# single_key_module.net
KiCad netlist of a schematic drawn in EAGLE
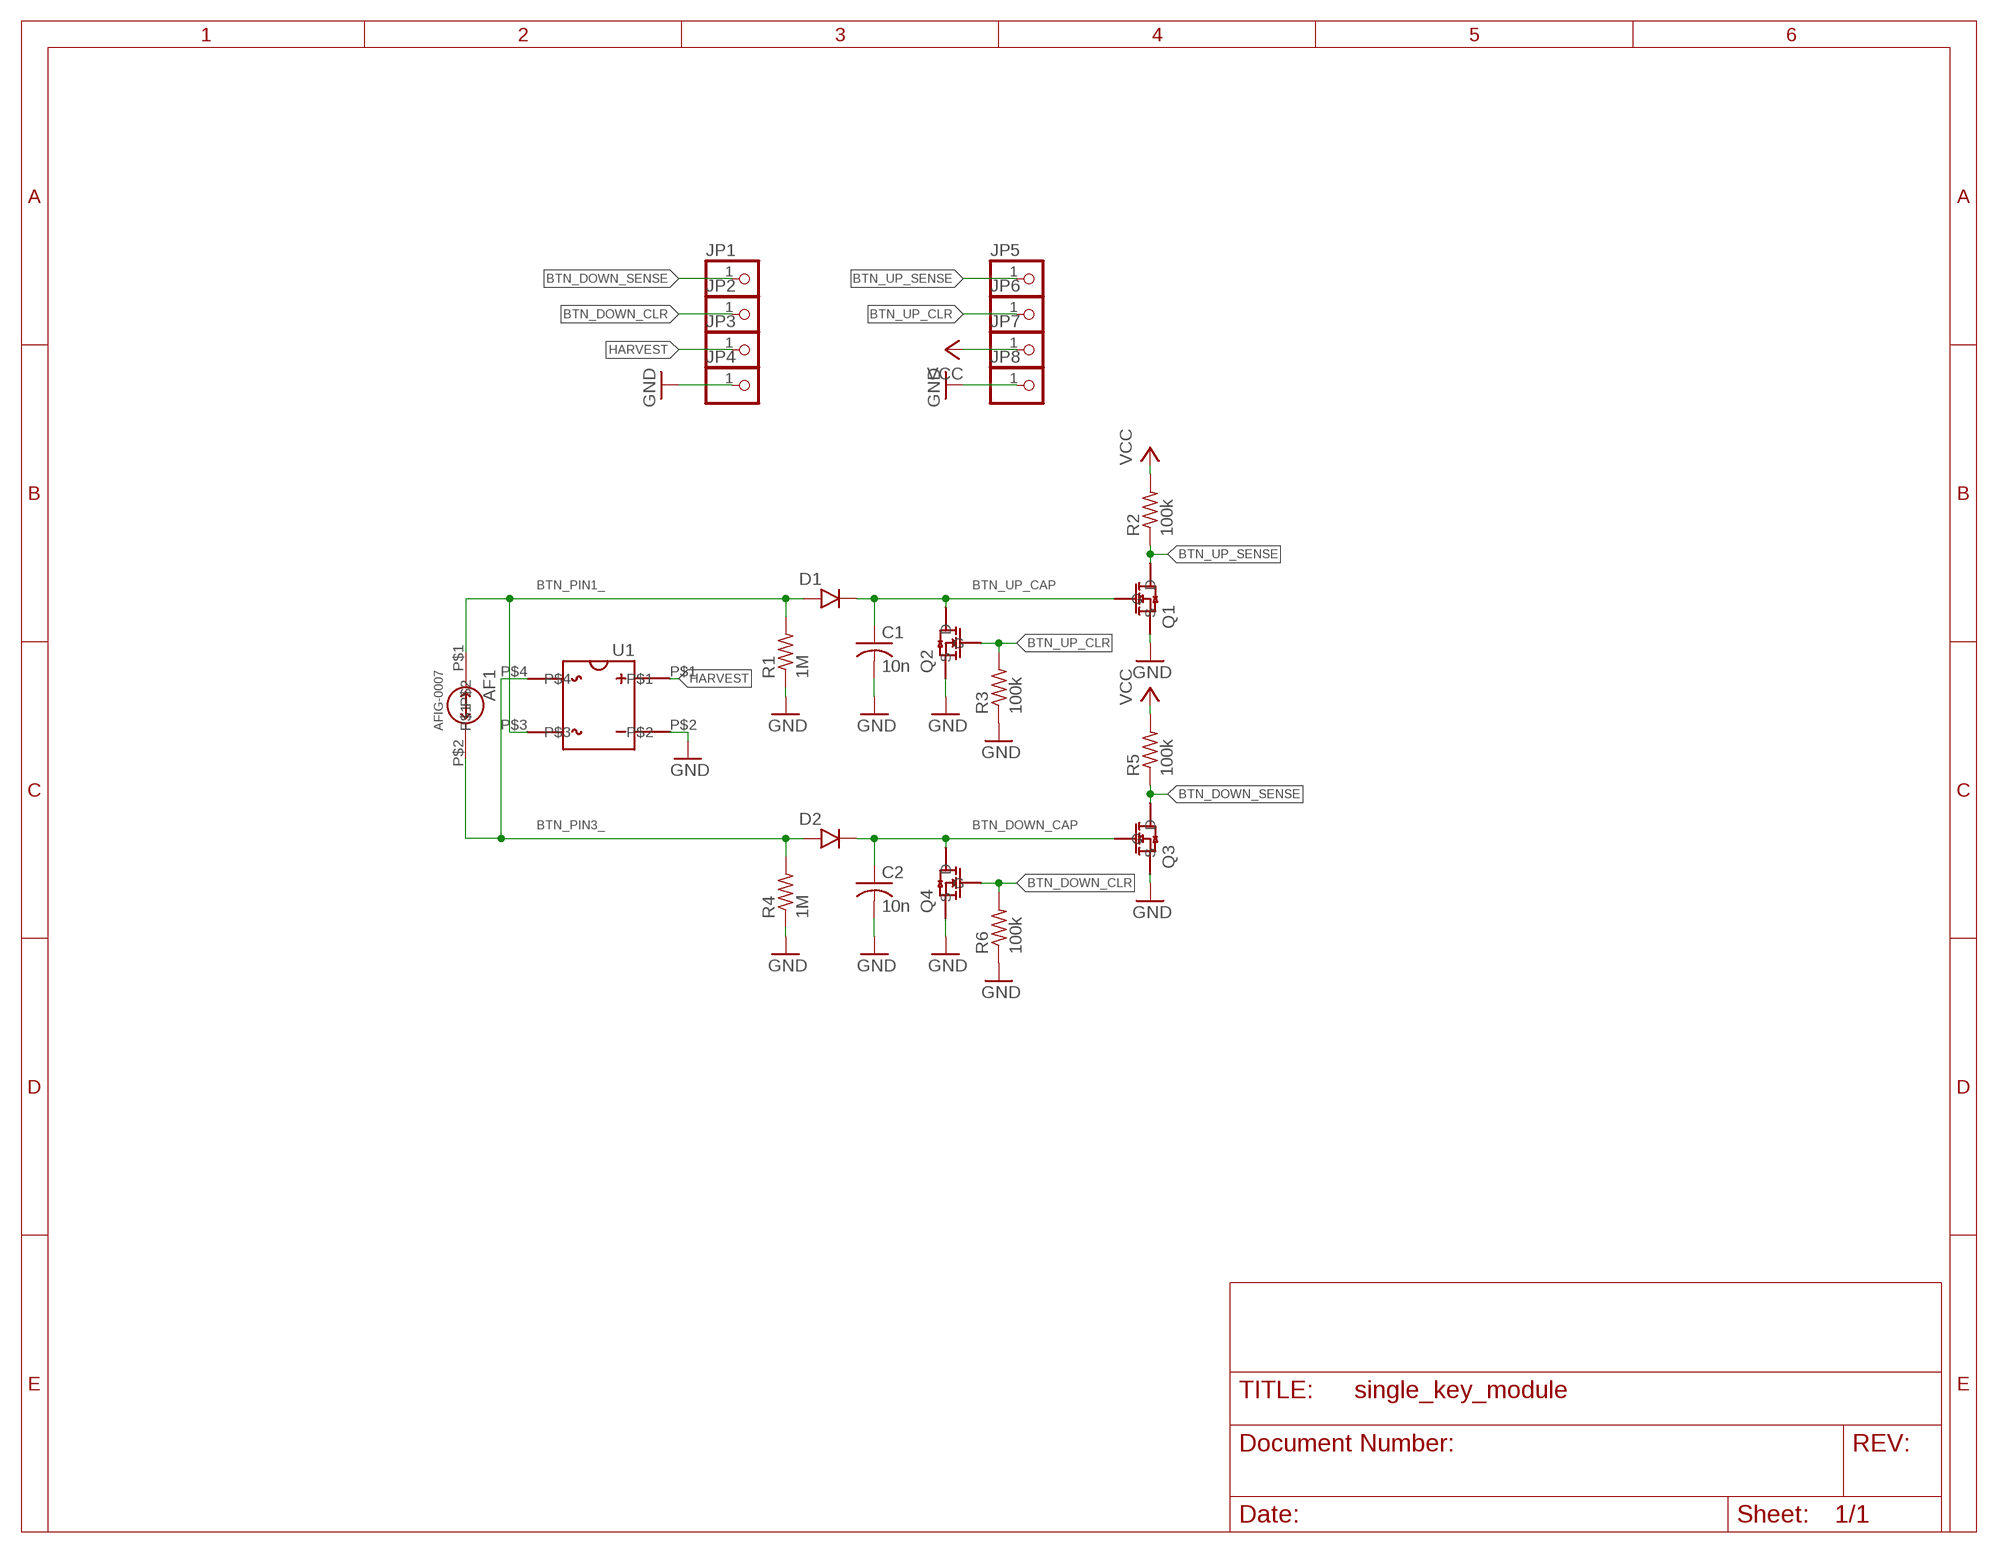
[diagram p0: schematic, sheet 1]

(export (version "E")
  (design (tool "Eeschema 10.0.6"))
  (components
    (comp (ref "AF1")
      (value "BUTTON-MOUNT")
      (footprint "eagle-import:BUTTON-MOUNT")
      (libsource (lib "eagle-import") (part "BUTTON-MOUNT"))
    )
    (comp (ref "C1")
      (value "10n")
      (footprint "eagle-import:C0402")
      (libsource (lib "eagle-import") (part "C-USC0402"))
    )
    (comp (ref "C2")
      (value "10n")
      (footprint "eagle-import:C0402")
      (libsource (lib "eagle-import") (part "C-USC0402"))
    )
    (comp (ref "D1")
      (value "DFLU1200")
      (footprint "eagle-import:DFLU1200")
      (libsource (lib "eagle-import") (part "DFLU1200"))
    )
    (comp (ref "D2")
      (value "DFLU1200")
      (footprint "eagle-import:DFLU1200")
      (libsource (lib "eagle-import") (part "DFLU1200"))
    )
    (comp (ref "JP1")
      (value "PINHD-1X1")
      (footprint "eagle-import:1X01")
      (libsource (lib "eagle-import") (part "PINHD-1X1"))
    )
    (comp (ref "JP2")
      (value "PINHD-1X1")
      (footprint "eagle-import:1X01")
      (libsource (lib "eagle-import") (part "PINHD-1X1"))
    )
    (comp (ref "JP3")
      (value "PINHD-1X1")
      (footprint "eagle-import:1X01")
      (libsource (lib "eagle-import") (part "PINHD-1X1"))
    )
    (comp (ref "JP4")
      (value "PINHD-1X1")
      (footprint "eagle-import:1X01")
      (libsource (lib "eagle-import") (part "PINHD-1X1"))
    )
    (comp (ref "JP5")
      (value "PINHD-1X1")
      (footprint "eagle-import:1X01")
      (libsource (lib "eagle-import") (part "PINHD-1X1"))
    )
    (comp (ref "JP6")
      (value "PINHD-1X1")
      (footprint "eagle-import:1X01")
      (libsource (lib "eagle-import") (part "PINHD-1X1"))
    )
    (comp (ref "JP7")
      (value "PINHD-1X1")
      (footprint "eagle-import:1X01")
      (libsource (lib "eagle-import") (part "PINHD-1X1"))
    )
    (comp (ref "JP8")
      (value "PINHD-1X1")
      (footprint "eagle-import:1X01")
      (libsource (lib "eagle-import") (part "PINHD-1X1"))
    )
    (comp (ref "Q1")
      (value "2N7002K-7")
      (footprint "eagle-import:2N7002K-7")
      (libsource (lib "eagle-import") (part "2N7002K-7"))
    )
    (comp (ref "Q2")
      (value "BSS138K")
      (footprint "eagle-import:BSS138K")
      (libsource (lib "eagle-import") (part "BSS138K"))
    )
    (comp (ref "Q3")
      (value "2N7002K-7")
      (footprint "eagle-import:2N7002K-7")
      (libsource (lib "eagle-import") (part "2N7002K-7"))
    )
    (comp (ref "Q4")
      (value "BSS138K")
      (footprint "eagle-import:BSS138K")
      (libsource (lib "eagle-import") (part "BSS138K"))
    )
    (comp (ref "R1")
      (value "1M")
      (footprint "eagle-import:R0402")
      (libsource (lib "eagle-import") (part "R-US_R0402"))
    )
    (comp (ref "R2")
      (value "100k")
      (footprint "eagle-import:R0402")
      (libsource (lib "eagle-import") (part "R-US_R0402"))
    )
    (comp (ref "R3")
      (value "100k")
      (footprint "eagle-import:R0402")
      (libsource (lib "eagle-import") (part "R-US_R0402"))
    )
    (comp (ref "R4")
      (value "1M")
      (footprint "eagle-import:R0402")
      (libsource (lib "eagle-import") (part "R-US_R0402"))
    )
    (comp (ref "R5")
      (value "100k")
      (footprint "eagle-import:R0402")
      (libsource (lib "eagle-import") (part "R-US_R0402"))
    )
    (comp (ref "R6")
      (value "100k")
      (footprint "eagle-import:R0402")
      (libsource (lib "eagle-import") (part "R-US_R0402"))
    )
    (comp (ref "U1")
      (value "CDBHD140L-G")
      (footprint "eagle-import:CDBHDXX0L-G")
      (libsource (lib "eagle-import") (part "CDBHD140L-G"))
    )
  )
  (nets
    (net (code "1") (name "/BTN_DOWN_CAP") (class "Default")
      (node (ref "C2") (pin "1") (pinfunction "1_1") (pintype "passive"))
      (node (ref "D2") (pin "K") (pinfunction "K_K") (pintype "bidirectional"))
      (node (ref "Q3") (pin "G") (pinfunction "G_G") (pintype "bidirectional"))
      (node (ref "Q4") (pin "D") (pinfunction "D_D") (pintype "bidirectional"))
    )
    (net (code "2") (name "/BTN_PIN1_") (class "Default")
      (node (ref "AF1") (pin "P$1") (pinfunction "P$1_P$1") (pintype "bidirectional"))
      (node (ref "D1") (pin "A") (pinfunction "A_A") (pintype "bidirectional"))
      (node (ref "R1") (pin "2") (pinfunction "2_2") (pintype "passive"))
      (node (ref "U1") (pin "P$3") (pinfunction "P$3_P$3") (pintype "bidirectional"))
    )
    (net (code "3") (name "/BTN_PIN3_") (class "Default")
      (node (ref "AF1") (pin "P$2") (pinfunction "P$2_P$2") (pintype "bidirectional"))
      (node (ref "D2") (pin "A") (pinfunction "A_A") (pintype "bidirectional"))
      (node (ref "R4") (pin "2") (pinfunction "2_2") (pintype "passive"))
      (node (ref "U1") (pin "P$4") (pinfunction "P$4_P$4") (pintype "bidirectional"))
    )
    (net (code "4") (name "/BTN_UP_CAP") (class "Default")
      (node (ref "C1") (pin "1") (pinfunction "1_1") (pintype "passive"))
      (node (ref "D1") (pin "K") (pinfunction "K_K") (pintype "bidirectional"))
      (node (ref "Q1") (pin "G") (pinfunction "G_G") (pintype "bidirectional"))
      (node (ref "Q2") (pin "D") (pinfunction "D_D") (pintype "bidirectional"))
    )
    (net (code "5") (name "BTN_DOWN_CLR") (class "Default")
      (node (ref "JP2") (pin "1") (pinfunction "1_1") (pintype "passive"))
      (node (ref "Q4") (pin "G") (pinfunction "G_G") (pintype "bidirectional"))
      (node (ref "R6") (pin "2") (pinfunction "2_2") (pintype "passive"))
    )
    (net (code "6") (name "BTN_DOWN_SENSE") (class "Default")
      (node (ref "JP1") (pin "1") (pinfunction "1_1") (pintype "passive"))
      (node (ref "Q3") (pin "D") (pinfunction "D_D") (pintype "bidirectional"))
      (node (ref "R5") (pin "1") (pinfunction "1_1") (pintype "passive"))
    )
    (net (code "7") (name "BTN_UP_CLR") (class "Default")
      (node (ref "JP6") (pin "1") (pinfunction "1_1") (pintype "passive"))
      (node (ref "Q2") (pin "G") (pinfunction "G_G") (pintype "bidirectional"))
      (node (ref "R3") (pin "2") (pinfunction "2_2") (pintype "passive"))
    )
    (net (code "8") (name "BTN_UP_SENSE") (class "Default")
      (node (ref "JP5") (pin "1") (pinfunction "1_1") (pintype "passive"))
      (node (ref "Q1") (pin "D") (pinfunction "D_D") (pintype "bidirectional"))
      (node (ref "R2") (pin "1") (pinfunction "1_1") (pintype "passive"))
    )
    (net (code "9") (name "GND") (class "Default")
      (node (ref "C1") (pin "2") (pinfunction "2_2") (pintype "passive"))
      (node (ref "C2") (pin "2") (pinfunction "2_2") (pintype "passive"))
      (node (ref "JP4") (pin "1") (pinfunction "1_1") (pintype "passive"))
      (node (ref "JP8") (pin "1") (pinfunction "1_1") (pintype "passive"))
      (node (ref "Q1") (pin "S") (pinfunction "S_S") (pintype "bidirectional"))
      (node (ref "Q2") (pin "S") (pinfunction "S_S") (pintype "bidirectional"))
      (node (ref "Q3") (pin "S") (pinfunction "S_S") (pintype "bidirectional"))
      (node (ref "Q4") (pin "S") (pinfunction "S_S") (pintype "bidirectional"))
      (node (ref "R1") (pin "1") (pinfunction "1_1") (pintype "passive"))
      (node (ref "R3") (pin "1") (pinfunction "1_1") (pintype "passive"))
      (node (ref "R4") (pin "1") (pinfunction "1_1") (pintype "passive"))
      (node (ref "R6") (pin "1") (pinfunction "1_1") (pintype "passive"))
      (node (ref "U1") (pin "P$2") (pinfunction "P$2_P$2") (pintype "bidirectional"))
    )
    (net (code "10") (name "HARVEST") (class "Default")
      (node (ref "JP3") (pin "1") (pinfunction "1_1") (pintype "passive"))
      (node (ref "U1") (pin "P$1") (pinfunction "P$1_P$1") (pintype "bidirectional"))
    )
    (net (code "11") (name "VCC") (class "Default")
      (node (ref "JP7") (pin "1") (pinfunction "1_1") (pintype "passive"))
      (node (ref "R2") (pin "2") (pinfunction "2_2") (pintype "passive"))
      (node (ref "R5") (pin "2") (pinfunction "2_2") (pintype "passive"))
    )
  )
)
